# ethernet.net
KiCad netlist of a schematic drawn in Altium Designer
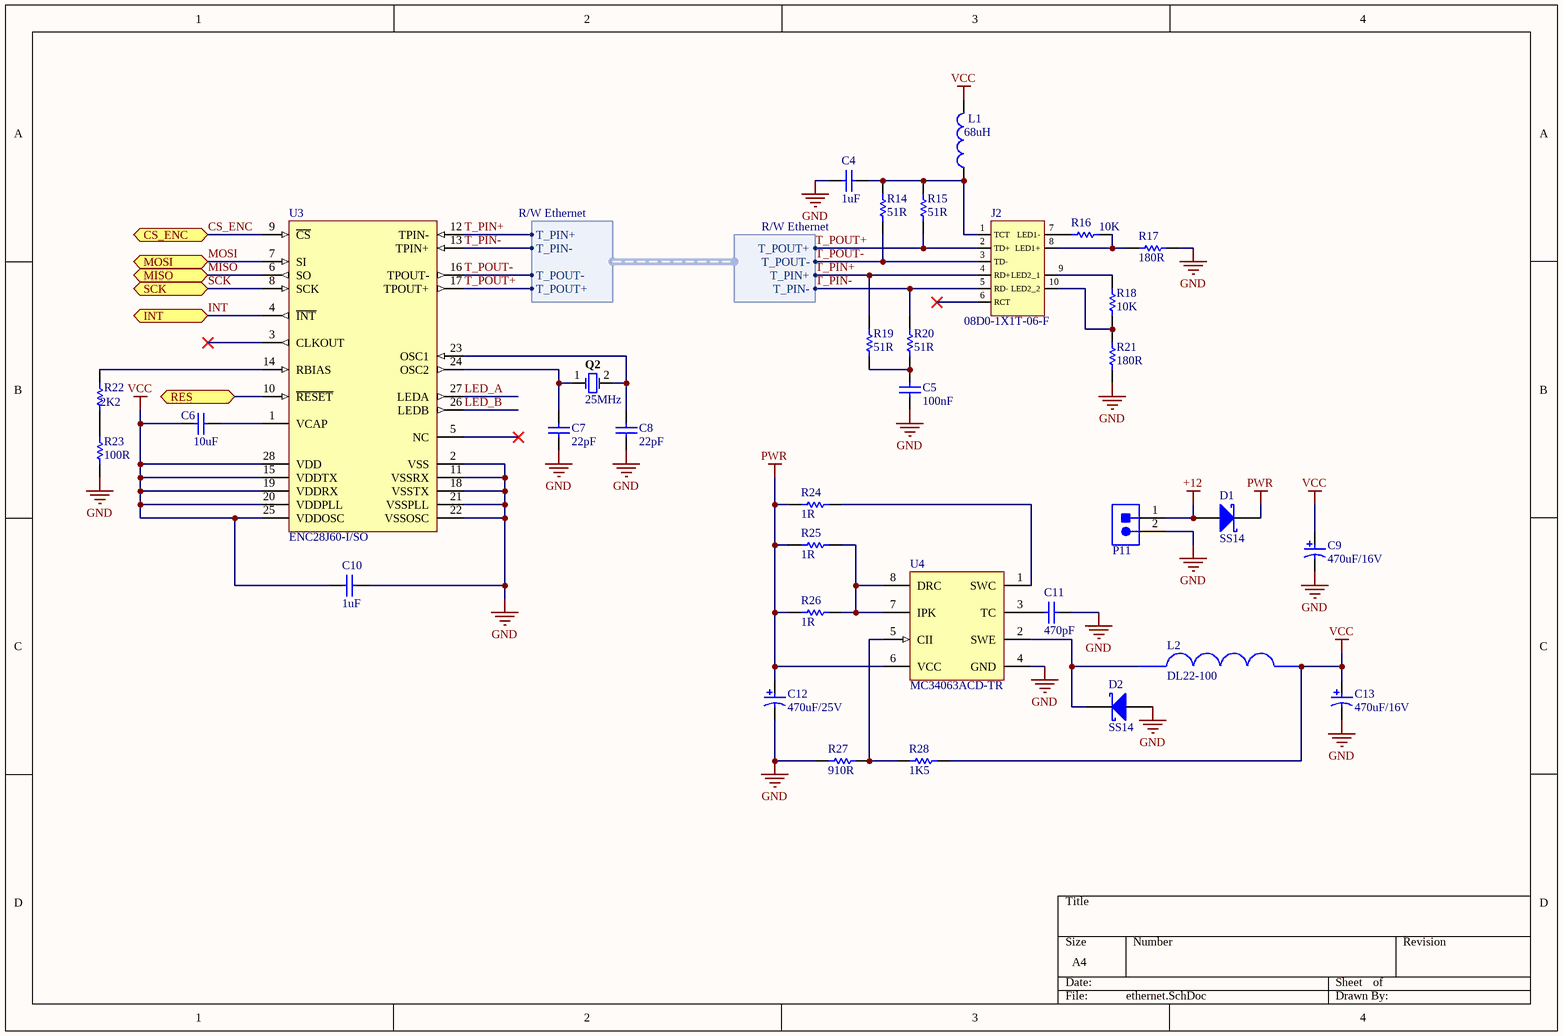
[diagram p0: ethernet.SchDoc]

(export (version "E")
  (design (tool "Eeschema 10.0.6"))
  (components
    (comp (ref "C4")
      (value "1uF")
      (footprint "CAPC1206(3216)150_L")
      (description "CAP 1uF 6.3V ±5% 1206 (3216 Metric) Thickness 1.45mm SMD")
      (fields (field (name "TOLERANCE") "Â±5%"))
      (libsource (lib "Altium Content Vault") (part "CAP"))
    )
    (comp (ref "C5")
      (value "100nF")
      (footprint "CAPC1206(3216)190_L")
      (description "CAP 100nF 10V ±1% 1206 (3216 Metric) Thickness 1.9mm SMD")
      (fields (field (name "TOLERANCE") "Â±1%"))
      (libsource (lib "Altium Content Vault") (part "CAP"))
    )
    (comp (ref "C6")
      (value "10uF")
      (footprint "CAPC1206(3216)190_L")
      (description "CAP 10uF 6.3V ±5% 1206 (3216 Metric) Thickness 1.9mm SMD")
      (fields (field (name "TOLERANCE") "Â±5%"))
      (libsource (lib "Altium Content Vault") (part "CAP"))
    )
    (comp (ref "C7")
      (value "22pF")
      (footprint "CAPC1206(3216)100_L")
      (description "CAP 22pF 10V ±0.25pF 1206 (3216 Metric) Thickness 1mm SMD")
      (fields (field (name "TOLERANCE") "Â±0.25pF"))
      (libsource (lib "Altium Content Vault") (part "CAP"))
    )
    (comp (ref "C8")
      (value "22pF")
      (footprint "CAPC1206(3216)100_L")
      (description "CAP 22pF 10V ±0.25pF 1206 (3216 Metric) Thickness 1mm SMD")
      (fields (field (name "TOLERANCE") "Â±0.25pF"))
      (libsource (lib "Altium Content Vault") (part "CAP"))
    )
    (comp (ref "C9")
      (value "470uF/16V")
      (footprint "PNSC-FK-V-F_V")
      (fields (field (name "MANUFACTURER") "Panasonic"))
      (libsource (lib "Altium Content Vault") (part "CAP-P-2"))
    )
    (comp (ref "C10")
      (value "1uF")
      (footprint "CAPC1206(3216)130_L")
      (description "CAP 1uF 10V ±5% 1206 (3216 Metric) Thickness 1.3mm SMD")
      (fields (field (name "TOLERANCE") "Â±5%"))
      (libsource (lib "Altium Content Vault") (part "CAP"))
    )
    (comp (ref "C11")
      (value "470pF")
      (footprint "CAPC1206(3216)100_L")
      (description "CAP 470pF 10V ±1% 1206 (3216 Metric) Thickness 1mm SMD")
      (fields (field (name "TOLERANCE") "Â±1%"))
      (libsource (lib "Altium Content Vault") (part "CAP"))
    )
    (comp (ref "C12")
      (value "470uF/25V")
      (footprint "NIC-CAPA2-10X10_V")
      (fields (field (name "PARTNUMBER") "UUD1E471MNL1GS") (field (name "MANUFACTURER") "Nichicon"))
      (libsource (lib "Altium Content Vault") (part "NIC-CAP-P-2"))
    )
    (comp (ref "C13")
      (value "470uF/16V")
      (footprint "PNSC-FK-V-F_V")
      (fields (field (name "MANUFACTURER") "Panasonic"))
      (libsource (lib "Altium Content Vault") (part "CAP-P-2"))
    )
    (comp (ref "D1")
      (value "SS14")
      (footprint "FAIR-DO-214AC-2_V")
      (description "Schottky Rectifier, 1.1 W, -65 to 125 degC, 2-Pin SMD, RoHS, Tape and Reel")
      (fields (field (name "MANUFACTURER") "Fairchild"))
      (libsource (lib "Altium Content Vault") (part "DSKY-KA-2"))
    )
    (comp (ref "D2")
      (value "SS14")
      (footprint "FAIR-DO-214AC-2_V")
      (description "Schottky Rectifier, 1.1 W, -65 to 125 degC, 2-Pin SMD, RoHS, Tape and Reel")
      (fields (field (name "MANUFACTURER") "Fairchild"))
      (libsource (lib "Altium Content Vault") (part "DSKY-KA-2"))
    )
    (comp (ref "J2")
      (value "08D0-1X1T-06-F")
      (footprint "PCB_08D0-1X1T-06-F")
      (libsource (lib "PKSchlib") (part "08D0-1X1T-06-F"))
    )
    (comp (ref "L1")
      (value "68uH")
      (footprint "0603")
      (description "Inductor")
      (fields (field (name "PUBLISHER") "Altium Limited"))
      (libsource (lib "Miscellaneous Devices") (part "Inductor"))
    )
    (comp (ref "L2") (value "DL22-100") (footprint "DL22") (libsource (lib "Dodatkowe") (part "DL22-100")))
    (comp (ref "P11")
      (value "SCREW-5.0/5.08 2WAYS")
      (footprint "SCREW-5.0-2WAYS_V")
      (description "Socket, Screw Terminal Block, 2 Way, 5.0 mm Pitch, 90 Degree Angle, Through-Hole")
      (fields (field (name "MANUFACTURER") "No Vendor"))
      (libsource (lib "Altium Content Vault") (part "SCREW-2WAYS"))
    )
    (comp (ref "Q2")
      (value "25MHz")
      (footprint "JPY-HC-49US")
      (description "Crystal, 25 MHz, +/- 30 ppm, 22 pF, -20 to 70 degC, 2-Pin THD")
      (fields (field (name "MANUFACTURER") "Jing peng yuan"))
      (libsource (lib "Altium Content Vault") (part "XTAL-1-2-2"))
    )
    (comp (ref "R14")
      (value "51R")
      (footprint "RESC1206(3216)_L")
      (description "51R 0.25W 1% 1206 (3216 Metric)  SMD")
      (fields (field (name "TOLERANCE") "1 %") (field (name "POWER") "0.25 W"))
      (libsource (lib "Altium Content Vault") (part "RES"))
    )
    (comp (ref "R15")
      (value "51R")
      (footprint "RESC1206(3216)_L")
      (description "51R 0.25W 1% 1206 (3216 Metric)  SMD")
      (fields (field (name "TOLERANCE") "1 %") (field (name "POWER") "0.25 W"))
      (libsource (lib "Altium Content Vault") (part "RES"))
    )
    (comp (ref "R16")
      (value "10K")
      (footprint "RESC1206(3216)_L")
      (description "10K 0.25W 1% 1206 (3216 Metric)  SMD")
      (fields (field (name "POWER") "0.25 W") (field (name "TOLERANCE") "1 %"))
      (libsource (lib "Altium Content Vault") (part "RES"))
    )
    (comp (ref "R17")
      (value "180R")
      (footprint "RESC1206(3216)_L")
      (description "180R 0.25W 1% 1206 (3216 Metric)  SMD")
      (fields (field (name "TOLERANCE") "1 %") (field (name "POWER") "0.25 W"))
      (libsource (lib "Altium Content Vault") (part "RES"))
    )
    (comp (ref "R18")
      (value "10K")
      (footprint "RESC1206(3216)_L")
      (description "10K 0.25W 1% 1206 (3216 Metric)  SMD")
      (fields (field (name "POWER") "0.25 W") (field (name "TOLERANCE") "1 %"))
      (libsource (lib "Altium Content Vault") (part "RES"))
    )
    (comp (ref "R19")
      (value "51R")
      (footprint "RESC1206(3216)_L")
      (description "51R 0.25W 1% 1206 (3216 Metric)  SMD")
      (fields (field (name "TOLERANCE") "1 %") (field (name "POWER") "0.25 W"))
      (libsource (lib "Altium Content Vault") (part "RES"))
    )
    (comp (ref "R20")
      (value "51R")
      (footprint "RESC1206(3216)_L")
      (description "51R 0.25W 1% 1206 (3216 Metric)  SMD")
      (fields (field (name "TOLERANCE") "1 %") (field (name "POWER") "0.25 W"))
      (libsource (lib "Altium Content Vault") (part "RES"))
    )
    (comp (ref "R21")
      (value "180R")
      (footprint "RESC1206(3216)_L")
      (description "180R 0.25W 1% 1206 (3216 Metric)  SMD")
      (fields (field (name "TOLERANCE") "1 %") (field (name "POWER") "0.25 W"))
      (libsource (lib "Altium Content Vault") (part "RES"))
    )
    (comp (ref "R22")
      (value "2K2")
      (footprint "RESC1206(3216)_L")
      (description "2K2 0.25W 1% 1206 (3216 Metric)  SMD")
      (fields (field (name "POWER") "0.25 W") (field (name "TOLERANCE") "1 %"))
      (libsource (lib "Altium Content Vault") (part "RES"))
    )
    (comp (ref "R23")
      (value "100R")
      (footprint "RESC1206(3216)_L")
      (description "100R 0.25W 1% 1206 (3216 Metric)  SMD")
      (fields (field (name "TOLERANCE") "1 %") (field (name "POWER") "0.25 W"))
      (libsource (lib "Altium Content Vault") (part "RES"))
    )
    (comp (ref "R24")
      (value "1R")
      (footprint "RESC1206(3216)_L")
      (description "1R 0.25W 1% 1206 (3216 Metric)  SMD")
      (fields (field (name "POWER") "0.25 W") (field (name "TOLERANCE") "1 %"))
      (libsource (lib "Altium Content Vault") (part "RES"))
    )
    (comp (ref "R25")
      (value "1R")
      (footprint "RESC1206(3216)_L")
      (description "1R 0.25W 1% 1206 (3216 Metric)  SMD")
      (fields (field (name "POWER") "0.25 W") (field (name "TOLERANCE") "1 %"))
      (libsource (lib "Altium Content Vault") (part "RES"))
    )
    (comp (ref "R26")
      (value "1R")
      (footprint "RESC1206(3216)_L")
      (description "1R 0.25W 1% 1206 (3216 Metric)  SMD")
      (fields (field (name "POWER") "0.25 W") (field (name "TOLERANCE") "1 %"))
      (libsource (lib "Altium Content Vault") (part "RES"))
    )
    (comp (ref "R27")
      (value "910R")
      (footprint "RESC1206(3216)_L")
      (description "910R 0.25W 1% 1206 (3216 Metric)  SMD")
      (fields (field (name "POWER") "0.25 W") (field (name "TOLERANCE") "1 %"))
      (libsource (lib "Altium Content Vault") (part "RES"))
    )
    (comp (ref "R28")
      (value "1K5")
      (footprint "RESC1206(3216)_L")
      (description "1K5 0.25W 1% 1206 (3216 Metric)  SMD")
      (fields (field (name "TOLERANCE") "1 %") (field (name "POWER") "0.25 W"))
      (libsource (lib "Altium Content Vault") (part "RES"))
    )
    (comp (ref "U3")
      (value "ENC28J60-I/SO")
      (footprint "SOIC-SO28_L")
      (description "Stand-Alone Ethernet Controller with SPI Interface, 28-Pin SOIC, Industrial Temperature")
      (libsource (lib "Altium Content Vault") (part "COM-ENET-ENC28J60-28"))
    )
    (comp (ref "U4")
      (value "MC34063ACD-TR")
      (footprint "SO8_L")
      (description "DC/DC converter control circuit, 8-Pin SO, Tape and Reel")
      (libsource (lib "Altium Content Vault") (part "PM-SWREG-MC34063-IL8"))
    )
  )
  (nets
    (net (code "3") (name "+12") (class "Default")
      (node (ref "D1") (pin "2") (pinfunction "A_2") (pintype "passive"))
      (node (ref "P11") (pin "1") (pinfunction "1_1") (pintype "passive"))
    )
    (net (code "4") (name "/CS_ENC") (class "Default")
      (node (ref "U3") (pin "9") (pinfunction "~{CS}_9") (pintype "input"))
    )
    (net (code "5") (name "/INT") (class "Default")
      (node (ref "U3") (pin "4") (pinfunction "~{INT}_4") (pintype "output"))
    )
    (net (code "6") (name "/LED_A") (class "Default")
      (node (ref "U3") (pin "27") (pinfunction "LEDA_27") (pintype "output"))
    )
    (net (code "7") (name "/LED_B") (class "Default")
      (node (ref "U3") (pin "26") (pinfunction "LEDB_26") (pintype "output"))
    )
    (net (code "8") (name "/MISO") (class "Default")
      (node (ref "U3") (pin "6") (pinfunction "SO_6") (pintype "output"))
    )
    (net (code "9") (name "/MOSI") (class "Default")
      (node (ref "U3") (pin "7") (pinfunction "SI_7") (pintype "input"))
    )
    (net (code "10") (name "/RES") (class "Default")
      (node (ref "U3") (pin "10") (pinfunction "~{RESET}_10") (pintype "input"))
    )
    (net (code "11") (name "/SCK") (class "Default")
      (node (ref "U3") (pin "8") (pinfunction "SCK_8") (pintype "input"))
    )
    (net (code "12") (name "/T_PIN+") (class "Default")
      (node (ref "J2") (pin "4") (pinfunction "RD+_4") (pintype "passive"))
      (node (ref "R19") (pin "2") (pinfunction "2_2") (pintype "passive"))
      (node (ref "U3") (pin "12") (pinfunction "TPIN-_12") (pintype "input"))
    )
    (net (code "13") (name "/T_PIN-") (class "Default")
      (node (ref "J2") (pin "5") (pinfunction "RD-_5") (pintype "passive"))
      (node (ref "R20") (pin "2") (pinfunction "2_2") (pintype "passive"))
      (node (ref "U3") (pin "13") (pinfunction "TPIN+_13") (pintype "input"))
    )
    (net (code "14") (name "/T_POUT+") (class "Default")
      (node (ref "J2") (pin "2") (pinfunction "TD+_2") (pintype "passive"))
      (node (ref "R15") (pin "1") (pinfunction "1_1") (pintype "passive"))
      (node (ref "U3") (pin "17") (pinfunction "TPOUT+_17") (pintype "output"))
    )
    (net (code "15") (name "/T_POUT-") (class "Default")
      (node (ref "J2") (pin "3") (pinfunction "TD-_3") (pintype "passive"))
      (node (ref "R14") (pin "1") (pinfunction "1_1") (pintype "passive"))
      (node (ref "U3") (pin "16") (pinfunction "TPOUT-_16") (pintype "output"))
    )
    (net (code "17") (name "GND") (class "Default")
      (node (ref "C10") (pin "1") (pinfunction "1_1") (pintype "passive"))
      (node (ref "C11") (pin "2") (pinfunction "2_2") (pintype "passive"))
      (node (ref "C12") (pin "2") (pinfunction "2_2") (pintype "passive"))
      (node (ref "C13") (pin "2") (pinfunction "2_2") (pintype "passive"))
      (node (ref "C4") (pin "1") (pinfunction "1_1") (pintype "passive"))
      (node (ref "C5") (pin "1") (pinfunction "1_1") (pintype "passive"))
      (node (ref "C7") (pin "1") (pinfunction "1_1") (pintype "passive"))
      (node (ref "C8") (pin "1") (pinfunction "1_1") (pintype "passive"))
      (node (ref "C9") (pin "2") (pinfunction "2_2") (pintype "passive"))
      (node (ref "D2") (pin "2") (pinfunction "A_2") (pintype "passive"))
      (node (ref "P11") (pin "2") (pinfunction "2_2") (pintype "passive"))
      (node (ref "R17") (pin "2") (pinfunction "2_2") (pintype "passive"))
      (node (ref "R21") (pin "1") (pinfunction "1_1") (pintype "passive"))
      (node (ref "R23") (pin "1") (pinfunction "1_1") (pintype "passive"))
      (node (ref "R27") (pin "1") (pinfunction "1_1") (pintype "passive"))
      (node (ref "U3") (pin "11") (pinfunction "VSSRX_11") (pintype "power_in"))
      (node (ref "U3") (pin "18") (pinfunction "VSSTX_18") (pintype "power_in"))
      (node (ref "U3") (pin "2") (pinfunction "VSS_2") (pintype "power_in"))
      (node (ref "U3") (pin "21") (pinfunction "VSSPLL_21") (pintype "power_in"))
      (node (ref "U3") (pin "22") (pinfunction "VSSOSC_22") (pintype "power_in"))
      (node (ref "U4") (pin "4") (pinfunction "GND_4") (pintype "power_in"))
    )
    (net (code "18") (name "Net-(C5-Pad2)") (class "Default")
      (node (ref "C5") (pin "2") (pinfunction "2_2") (pintype "passive"))
      (node (ref "R19") (pin "1") (pinfunction "1_1") (pintype "passive"))
      (node (ref "R20") (pin "1") (pinfunction "1_1") (pintype "passive"))
    )
    (net (code "19") (name "Net-(D2-K)") (class "Default")
      (node (ref "D2") (pin "1") (pinfunction "K_1") (pintype "passive"))
      (node (ref "L2") (pin "1") (pinfunction "1_1") (pintype "passive"))
      (node (ref "U4") (pin "2") (pinfunction "SWE_2") (pintype "open_emitter"))
    )
    (net (code "20") (name "Net-(J2-LED1+)") (class "Default")
      (node (ref "J2") (pin "8") (pinfunction "LED1+_8") (pintype "passive"))
      (node (ref "R16") (pin "1") (pinfunction "1_1") (pintype "passive"))
      (node (ref "R17") (pin "1") (pinfunction "1_1") (pintype "passive"))
    )
    (net (code "21") (name "Net-(J2-LED1-)") (class "Default")
      (node (ref "J2") (pin "7") (pinfunction "LED1-_7") (pintype "passive"))
      (node (ref "R16") (pin "2") (pinfunction "2_2") (pintype "passive"))
    )
    (net (code "22") (name "Net-(J2-LED2_1)") (class "Default")
      (node (ref "J2") (pin "9") (pinfunction "LED2_1_9") (pintype "passive"))
      (node (ref "R18") (pin "2") (pinfunction "2_2") (pintype "passive"))
    )
    (net (code "23") (name "Net-(J2-LED2_2)") (class "Default")
      (node (ref "J2") (pin "10") (pinfunction "LED2_2_10") (pintype "passive"))
      (node (ref "R18") (pin "1") (pinfunction "1_1") (pintype "passive"))
      (node (ref "R21") (pin "2") (pinfunction "2_2") (pintype "passive"))
    )
    (net (code "24") (name "Net-(J2-TCT)") (class "Default")
      (node (ref "C4") (pin "2") (pinfunction "2_2") (pintype "passive"))
      (node (ref "J2") (pin "1") (pinfunction "TCT_1") (pintype "passive"))
      (node (ref "L1") (pin "1") (pinfunction "1_1") (pintype "passive"))
      (node (ref "R14") (pin "2") (pinfunction "2_2") (pintype "passive"))
      (node (ref "R15") (pin "2") (pinfunction "2_2") (pintype "passive"))
    )
    (net (code "25") (name "Net-(R22-Pad1)") (class "Default")
      (node (ref "R22") (pin "1") (pinfunction "1_1") (pintype "passive"))
      (node (ref "R23") (pin "2") (pinfunction "2_2") (pintype "passive"))
    )
    (net (code "26") (name "Net-(U3-OSC1)") (class "Default")
      (node (ref "C8") (pin "2") (pinfunction "2_2") (pintype "passive"))
      (node (ref "Q2") (pin "2") (pinfunction "2_2") (pintype "passive"))
      (node (ref "U3") (pin "23") (pinfunction "OSC1_23") (pintype "input"))
    )
    (net (code "27") (name "Net-(U3-OSC2)") (class "Default")
      (node (ref "C7") (pin "2") (pinfunction "2_2") (pintype "passive"))
      (node (ref "Q2") (pin "1") (pinfunction "1_1") (pintype "passive"))
      (node (ref "U3") (pin "24") (pinfunction "OSC2_24") (pintype "output"))
    )
    (net (code "28") (name "Net-(U3-RBIAS)") (class "Default")
      (node (ref "R22") (pin "2") (pinfunction "2_2") (pintype "passive"))
      (node (ref "U3") (pin "14") (pinfunction "RBIAS_14") (pintype "input"))
    )
    (net (code "29") (name "Net-(U3-VCAP)") (class "Default")
      (node (ref "C6") (pin "2") (pinfunction "2_2") (pintype "passive"))
      (node (ref "U3") (pin "1") (pinfunction "VCAP_1") (pintype "power_in"))
    )
    (net (code "30") (name "Net-(U4-CII)") (class "Default")
      (node (ref "R27") (pin "2") (pinfunction "2_2") (pintype "passive"))
      (node (ref "R28") (pin "1") (pinfunction "1_1") (pintype "passive"))
      (node (ref "U4") (pin "5") (pinfunction "CII_5") (pintype "input"))
    )
    (net (code "31") (name "Net-(U4-DRC)") (class "Default")
      (node (ref "R25") (pin "2") (pinfunction "2_2") (pintype "passive"))
      (node (ref "R26") (pin "2") (pinfunction "2_2") (pintype "passive"))
      (node (ref "U4") (pin "7") (pinfunction "IPK_7") (pintype "passive"))
      (node (ref "U4") (pin "8") (pinfunction "DRC_8") (pintype "open_collector"))
    )
    (net (code "32") (name "Net-(U4-SWC)") (class "Default")
      (node (ref "R24") (pin "2") (pinfunction "2_2") (pintype "passive"))
      (node (ref "U4") (pin "1") (pinfunction "SWC_1") (pintype "open_collector"))
    )
    (net (code "33") (name "Net-(U4-TC)") (class "Default")
      (node (ref "C11") (pin "1") (pinfunction "1_1") (pintype "passive"))
      (node (ref "U4") (pin "3") (pinfunction "TC_3") (pintype "passive"))
    )
    (net (code "34") (name "PWR") (class "Default")
      (node (ref "C12") (pin "1") (pinfunction "1_1") (pintype "passive"))
      (node (ref "D1") (pin "1") (pinfunction "K_1") (pintype "passive"))
      (node (ref "R24") (pin "1") (pinfunction "1_1") (pintype "passive"))
      (node (ref "R25") (pin "1") (pinfunction "1_1") (pintype "passive"))
      (node (ref "R26") (pin "1") (pinfunction "1_1") (pintype "passive"))
      (node (ref "U4") (pin "6") (pinfunction "VCC_6") (pintype "power_in"))
    )
    (net (code "35") (name "VCC") (class "Default")
      (node (ref "C10") (pin "2") (pinfunction "2_2") (pintype "passive"))
      (node (ref "C13") (pin "1") (pinfunction "1_1") (pintype "passive"))
      (node (ref "C6") (pin "1") (pinfunction "1_1") (pintype "passive"))
      (node (ref "C9") (pin "1") (pinfunction "1_1") (pintype "passive"))
      (node (ref "L1") (pin "2") (pinfunction "2_2") (pintype "passive"))
      (node (ref "L2") (pin "2") (pinfunction "2_2") (pintype "passive"))
      (node (ref "R28") (pin "2") (pinfunction "2_2") (pintype "passive"))
      (node (ref "U3") (pin "15") (pinfunction "VDDTX_15") (pintype "power_in"))
      (node (ref "U3") (pin "19") (pinfunction "VDDRX_19") (pintype "power_in"))
      (node (ref "U3") (pin "20") (pinfunction "VDDPLL_20") (pintype "power_in"))
      (node (ref "U3") (pin "25") (pinfunction "VDDOSC_25") (pintype "power_in"))
      (node (ref "U3") (pin "28") (pinfunction "VDD_28") (pintype "power_in"))
    )
    (net (code "36") (name "unconnected-(J2-RCT-Pad6)") (class "Default")
      (node (ref "J2") (pin "6") (pinfunction "RCT_6") (pintype "passive+no_connect"))
    )
    (net (code "37") (name "unconnected-(U3-CLKOUT-Pad3)") (class "Default")
      (node (ref "U3") (pin "3") (pinfunction "CLKOUT_3") (pintype "output+no_connect"))
    )
    (net (code "38") (name "unconnected-(U3-NC-Pad5)") (class "Default")
      (node (ref "U3") (pin "5") (pinfunction "NC_5") (pintype "passive+no_connect"))
    )
  )
)
